# FlightControl.net
KiCad netlist of a schematic drawn in EAGLE
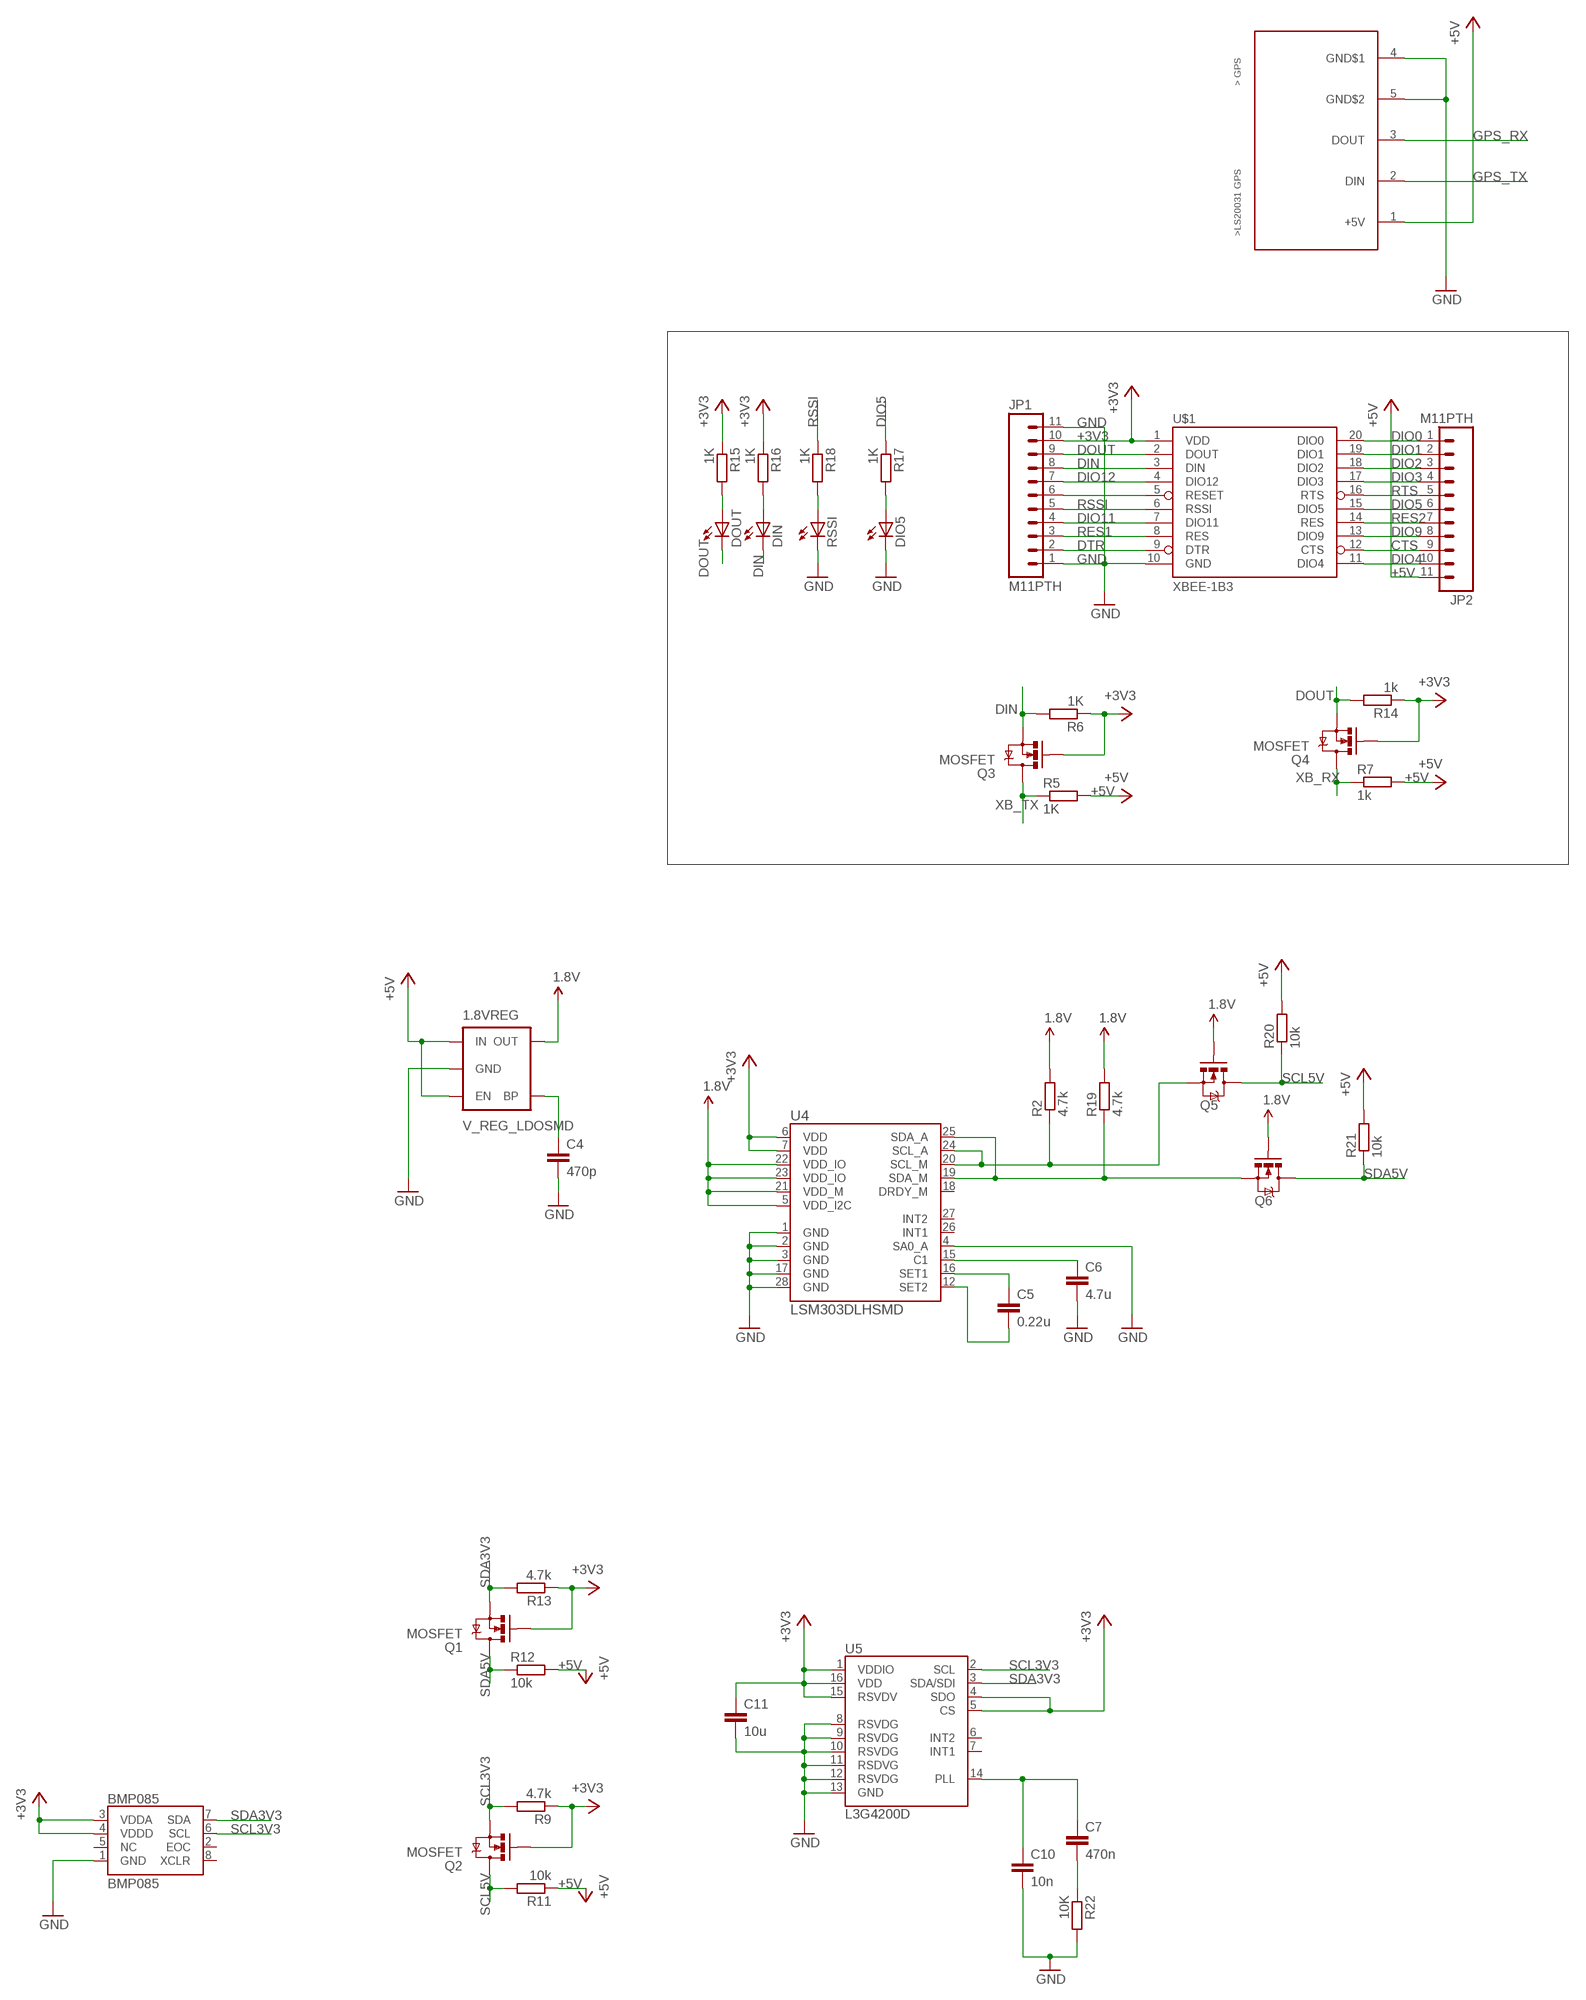
[diagram p0: schematic, sheet 1, part 1 of 2]
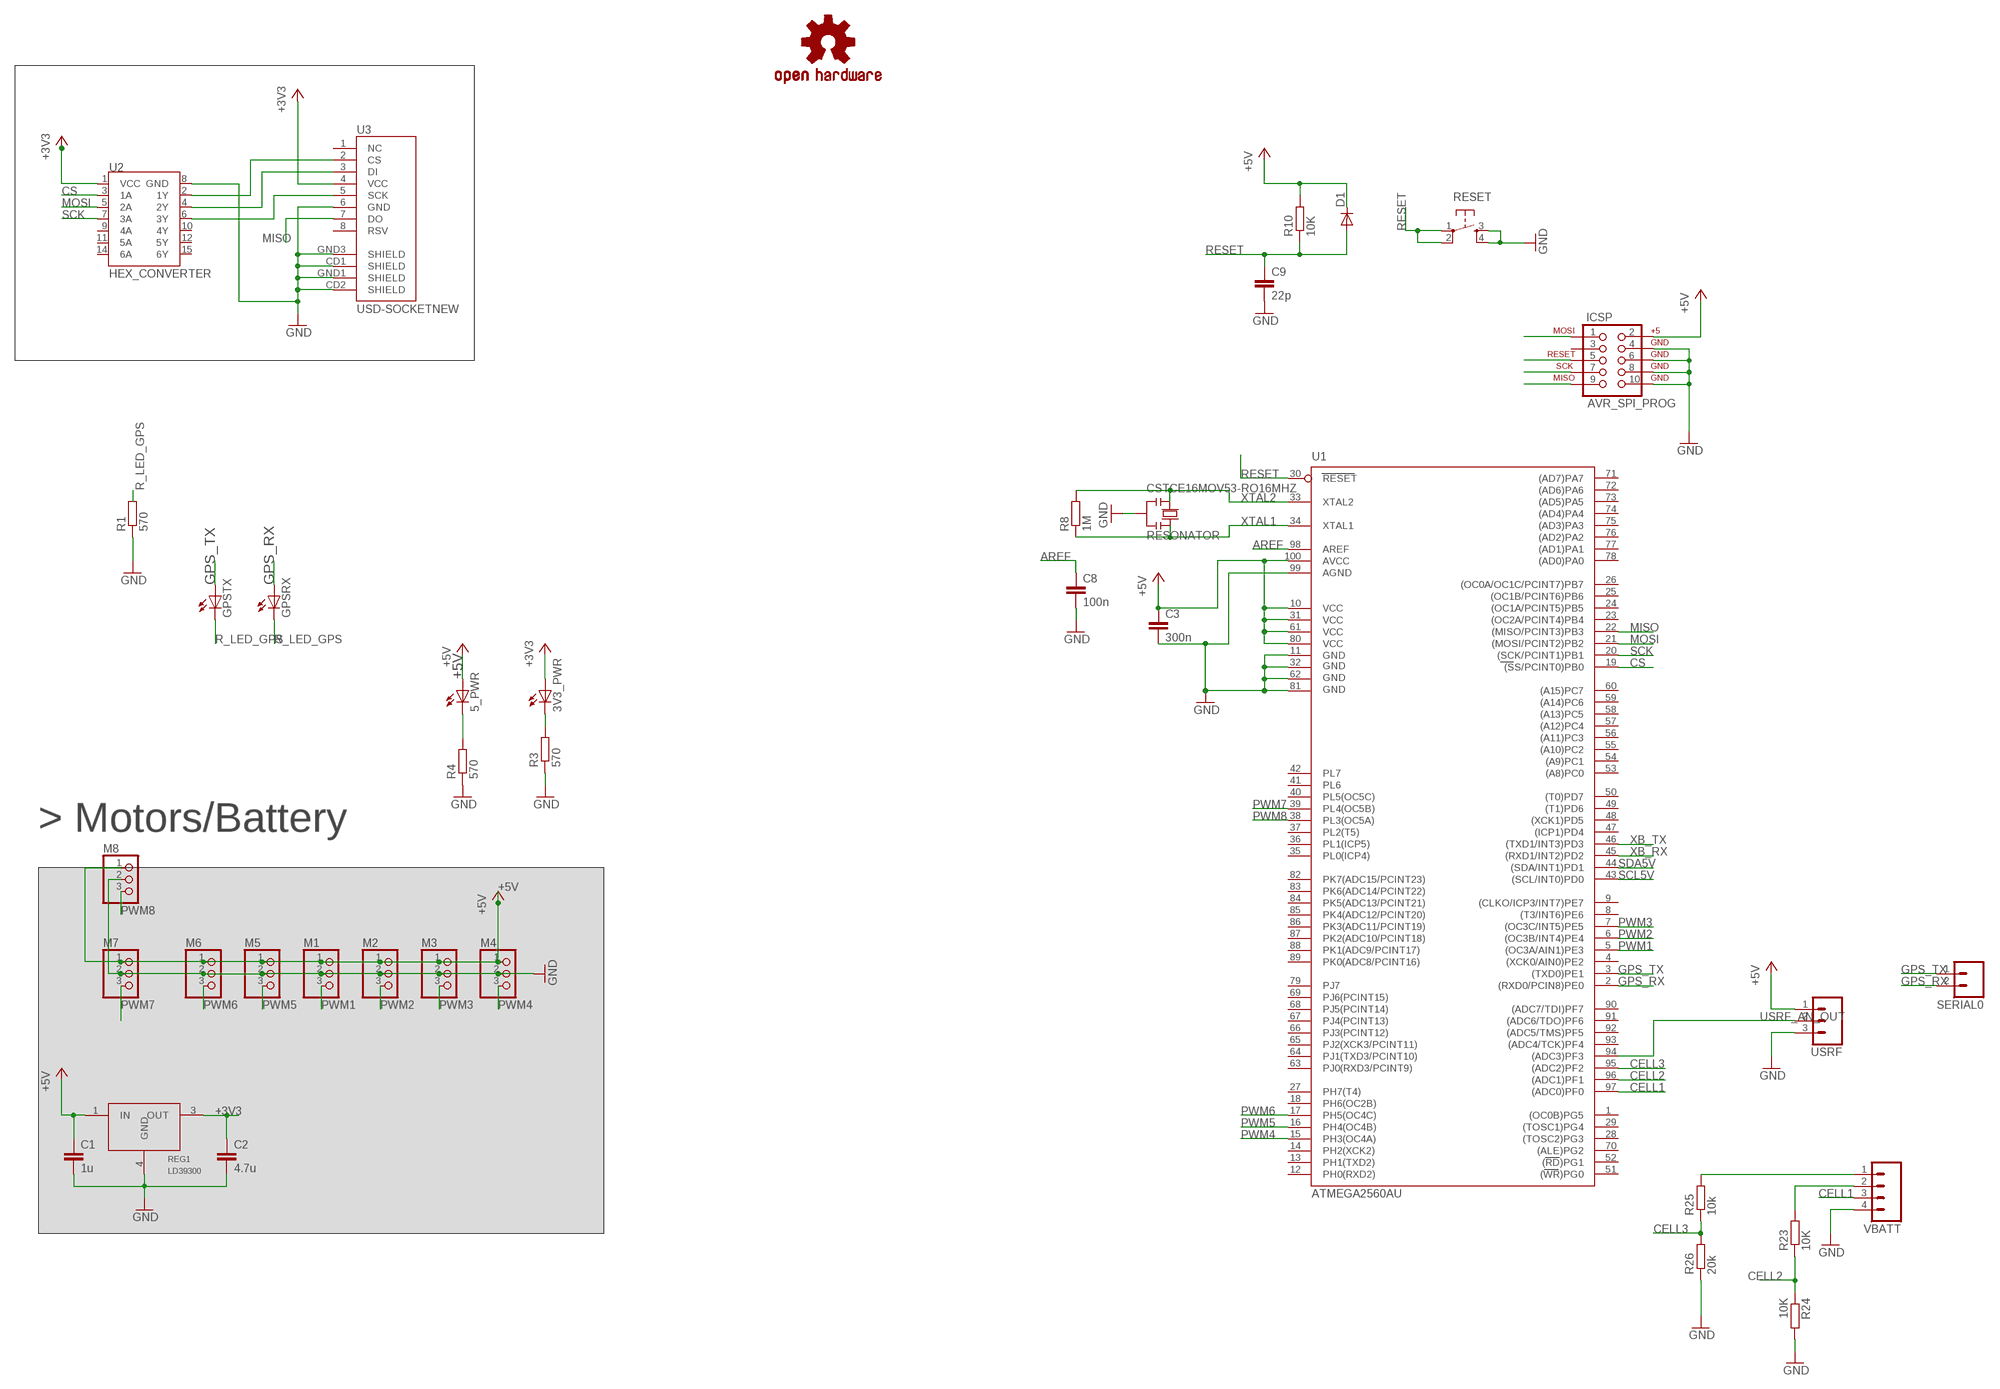
[diagram p1: schematic, sheet 1, part 2 of 2]

(export (version "E")
  (design (tool "Eeschema 10.0.6"))
  (components
    (comp (ref "1.8VREG")
      (value "V_REG_LDOSMD")
      (footprint "eagle-import:SOT23-5")
      (libsource (lib "eagle-import") (part "V_REG_LDOSMD"))
    )
    (comp (ref "3V3_PWR")
      (value "LEDCHIPLED_1206")
      (footprint "eagle-import:CHIPLED_1206")
      (libsource (lib "eagle-import") (part "LEDCHIPLED_1206"))
    )
    (comp (ref "5_PWR")
      (value "LEDCHIPLED_1206")
      (footprint "eagle-import:CHIPLED_1206")
      (libsource (lib "eagle-import") (part "LEDCHIPLED_1206"))
    )
    (comp (ref "BMP085")
      (value "BMP085")
      (footprint "eagle-import:BMP085")
      (libsource (lib "eagle-import") (part "BMP085"))
    )
    (comp (ref "C1")
      (value "1u")
      (footprint "eagle-import:C3216")
      (libsource (lib "eagle-import") (part "C-EUC3216"))
    )
    (comp (ref "C2")
      (value "4.7u")
      (footprint "eagle-import:C3216")
      (libsource (lib "eagle-import") (part "C-EUC3216"))
    )
    (comp (ref "C3")
      (value "300n")
      (footprint "eagle-import:C3216")
      (libsource (lib "eagle-import") (part "C-EUC3216"))
    )
    (comp (ref "C4")
      (value "470p")
      (footprint "eagle-import:C3216")
      (libsource (lib "eagle-import") (part "C-EUC3216"))
    )
    (comp (ref "C5")
      (value "0.22u")
      (footprint "eagle-import:C3216")
      (libsource (lib "eagle-import") (part "C-EUC3216"))
    )
    (comp (ref "C6")
      (value "4.7u")
      (footprint "eagle-import:C3216")
      (libsource (lib "eagle-import") (part "C-EUC3216"))
    )
    (comp (ref "C7")
      (value "470n")
      (footprint "eagle-import:C3216")
      (libsource (lib "eagle-import") (part "C-EUC3216"))
    )
    (comp (ref "C8")
      (value "100n")
      (footprint "eagle-import:C3216")
      (libsource (lib "eagle-import") (part "C-EUC3216"))
    )
    (comp (ref "C9")
      (value "22p")
      (footprint "eagle-import:C3216")
      (libsource (lib "eagle-import") (part "C-EUC3216"))
    )
    (comp (ref "C10")
      (value "10n")
      (footprint "eagle-import:C3216")
      (libsource (lib "eagle-import") (part "C-EUC3216"))
    )
    (comp (ref "C11")
      (value "10u")
      (footprint "eagle-import:C3216")
      (libsource (lib "eagle-import") (part "C-EUC3216"))
    )
    (comp (ref "CSTCE16MOV53-RO16MHZ")
      (value "RESONATOR")
      (footprint "eagle-import:RESONATOR")
      (libsource (lib "eagle-import") (part "RESONATORMU"))
    )
    (comp (ref "D1")
      (value "DIODE-MINIMELF")
      (footprint "eagle-import:MINIMELF")
      (libsource (lib "eagle-import") (part "DIODE-MINIMELF"))
    )
    (comp (ref "DIN")
      (value "LEDCHIPLED_1206")
      (footprint "eagle-import:CHIPLED_1206")
      (libsource (lib "eagle-import") (part "LEDCHIPLED_1206"))
    )
    (comp (ref "DIO5")
      (value "LEDCHIPLED_1206")
      (footprint "eagle-import:CHIPLED_1206")
      (libsource (lib "eagle-import") (part "LEDCHIPLED_1206"))
    )
    (comp (ref "DOUT")
      (value "LEDCHIPLED_1206")
      (footprint "eagle-import:CHIPLED_1206")
      (libsource (lib "eagle-import") (part "LEDCHIPLED_1206"))
    )
    (comp (ref "GPSRX")
      (value "LEDCHIPLED_1206")
      (footprint "eagle-import:CHIPLED_1206")
      (libsource (lib "eagle-import") (part "LEDCHIPLED_1206"))
    )
    (comp (ref "GPSTX")
      (value "LEDCHIPLED_1206")
      (footprint "eagle-import:CHIPLED_1206")
      (libsource (lib "eagle-import") (part "LEDCHIPLED_1206"))
    )
    (comp (ref "ICSP")
      (value "AVR_SPI_PROG")
      (footprint "eagle-import:AVR_ICSP")
      (libsource (lib "eagle-import") (part "AVR_SPI_PROG"))
    )
    (comp (ref "JP1")
      (value "M11PTH")
      (footprint "eagle-import:1X11")
      (libsource (lib "eagle-import") (part "M11PTH"))
    )
    (comp (ref "JP2")
      (value "M11PTH")
      (footprint "eagle-import:1X11")
      (libsource (lib "eagle-import") (part "M11PTH"))
    )
    (comp (ref "LOGO1")
      (value "OSHW-LOGOL")
      (footprint "eagle-import:OSHW-LOGO-L")
      (libsource (lib "eagle-import") (part "OSHW-LOGOL"))
    )
    (comp (ref "M1")
      (value "PINHD-1X3")
      (footprint "eagle-import:1X03")
      (libsource (lib "eagle-import") (part "PINHD-1X3"))
    )
    (comp (ref "M2")
      (value "PINHD-1X3")
      (footprint "eagle-import:1X03")
      (libsource (lib "eagle-import") (part "PINHD-1X3"))
    )
    (comp (ref "M3")
      (value "PINHD-1X3")
      (footprint "eagle-import:1X03")
      (libsource (lib "eagle-import") (part "PINHD-1X3"))
    )
    (comp (ref "M4")
      (value "PINHD-1X3")
      (footprint "eagle-import:1X03")
      (libsource (lib "eagle-import") (part "PINHD-1X3"))
    )
    (comp (ref "M5")
      (value "PINHD-1X3")
      (footprint "eagle-import:1X03")
      (libsource (lib "eagle-import") (part "PINHD-1X3"))
    )
    (comp (ref "M6")
      (value "PINHD-1X3")
      (footprint "eagle-import:1X03")
      (libsource (lib "eagle-import") (part "PINHD-1X3"))
    )
    (comp (ref "M7")
      (value "PINHD-1X3")
      (footprint "eagle-import:1X03")
      (libsource (lib "eagle-import") (part "PINHD-1X3"))
    )
    (comp (ref "M8")
      (value "PINHD-1X3")
      (footprint "eagle-import:1X03")
      (libsource (lib "eagle-import") (part "PINHD-1X3"))
    )
    (comp (ref "Q1")
      (value "MOSFET")
      (footprint "eagle-import:SOT23")
      (libsource (lib "eagle-import") (part "MOSFET-NCHANNELBSS138"))
    )
    (comp (ref "Q2")
      (value "MOSFET")
      (footprint "eagle-import:SOT23")
      (libsource (lib "eagle-import") (part "MOSFET-NCHANNELBSS138"))
    )
    (comp (ref "Q3")
      (value "MOSFET")
      (footprint "eagle-import:SOT23")
      (libsource (lib "eagle-import") (part "MOSFET-NCHANNELBSS138"))
    )
    (comp (ref "Q4")
      (value "MOSFET")
      (footprint "eagle-import:SOT23")
      (libsource (lib "eagle-import") (part "MOSFET-NCHANNELBSS138"))
    )
    (comp (ref "Q5")
      (value "MOSFET")
      (footprint "eagle-import:SOT23")
      (libsource (lib "eagle-import") (part "MOSFET-NCHANNELBSS138"))
    )
    (comp (ref "Q6")
      (value "MOSFET")
      (footprint "eagle-import:SOT23")
      (libsource (lib "eagle-import") (part "MOSFET-NCHANNELBSS138"))
    )
    (comp (ref "R1")
      (value "570")
      (footprint "eagle-import:R1206")
      (libsource (lib "eagle-import") (part "R-EU_R1206"))
    )
    (comp (ref "R2")
      (value "4.7k")
      (footprint "eagle-import:R1206")
      (libsource (lib "eagle-import") (part "R-EU_R1206"))
    )
    (comp (ref "R3")
      (value "570")
      (footprint "eagle-import:R1206")
      (libsource (lib "eagle-import") (part "R-EU_R1206"))
    )
    (comp (ref "R4")
      (value "570")
      (footprint "eagle-import:R1206")
      (libsource (lib "eagle-import") (part "R-EU_R1206"))
    )
    (comp (ref "R5")
      (value "1K")
      (footprint "eagle-import:R1206")
      (libsource (lib "eagle-import") (part "R-EU_R1206"))
    )
    (comp (ref "R6")
      (value "1K")
      (footprint "eagle-import:R1206")
      (libsource (lib "eagle-import") (part "R-EU_R1206"))
    )
    (comp (ref "R7")
      (value "1k")
      (footprint "eagle-import:R1206")
      (libsource (lib "eagle-import") (part "R-EU_R1206"))
    )
    (comp (ref "R8")
      (value "1M")
      (footprint "eagle-import:R1206")
      (libsource (lib "eagle-import") (part "R-EU_R1206"))
    )
    (comp (ref "R9")
      (value "4.7k")
      (footprint "eagle-import:R1206")
      (libsource (lib "eagle-import") (part "R-EU_R1206"))
    )
    (comp (ref "R10")
      (value "10K")
      (footprint "eagle-import:R1206")
      (libsource (lib "eagle-import") (part "R-EU_R1206"))
    )
    (comp (ref "R11")
      (value "10k")
      (footprint "eagle-import:R1206")
      (libsource (lib "eagle-import") (part "R-EU_R1206"))
    )
    (comp (ref "R12")
      (value "10k")
      (footprint "eagle-import:R1206")
      (libsource (lib "eagle-import") (part "R-EU_R1206"))
    )
    (comp (ref "R13")
      (value "4.7k")
      (footprint "eagle-import:R1206")
      (libsource (lib "eagle-import") (part "R-EU_R1206"))
    )
    (comp (ref "R14")
      (value "1k")
      (footprint "eagle-import:R1206")
      (libsource (lib "eagle-import") (part "R-EU_R1206"))
    )
    (comp (ref "R15")
      (value "1K")
      (footprint "eagle-import:R1206")
      (libsource (lib "eagle-import") (part "R-EU_R1206"))
    )
    (comp (ref "R16")
      (value "1K")
      (footprint "eagle-import:R1206")
      (libsource (lib "eagle-import") (part "R-EU_R1206"))
    )
    (comp (ref "R17")
      (value "1K")
      (footprint "eagle-import:R1206")
      (libsource (lib "eagle-import") (part "R-EU_R1206"))
    )
    (comp (ref "R18")
      (value "1K")
      (footprint "eagle-import:R1206")
      (libsource (lib "eagle-import") (part "R-EU_R1206"))
    )
    (comp (ref "R19")
      (value "4.7k")
      (footprint "eagle-import:R1206")
      (libsource (lib "eagle-import") (part "R-EU_R1206"))
    )
    (comp (ref "R20")
      (value "10k")
      (footprint "eagle-import:R1206")
      (libsource (lib "eagle-import") (part "R-EU_R1206"))
    )
    (comp (ref "R21")
      (value "10k")
      (footprint "eagle-import:R1206")
      (libsource (lib "eagle-import") (part "R-EU_R1206"))
    )
    (comp (ref "R22")
      (value "10K")
      (footprint "eagle-import:R1206")
      (libsource (lib "eagle-import") (part "R-EU_R1206"))
    )
    (comp (ref "R23")
      (value "10K")
      (footprint "eagle-import:R1206")
      (libsource (lib "eagle-import") (part "R-EU_R1206"))
    )
    (comp (ref "R24")
      (value "10K")
      (footprint "eagle-import:R1206")
      (libsource (lib "eagle-import") (part "R-EU_R1206"))
    )
    (comp (ref "R25")
      (value "10k")
      (footprint "eagle-import:R1206")
      (libsource (lib "eagle-import") (part "R-EU_R1206"))
    )
    (comp (ref "R26")
      (value "20k")
      (footprint "eagle-import:R1206")
      (libsource (lib "eagle-import") (part "R-EU_R1206"))
    )
    (comp (ref "REG1")
      (value "LD39300")
      (footprint "eagle-import:DPAK")
      (libsource (lib "eagle-import") (part "LD39300"))
    )
    (comp (ref "RESET")
      (value "TAC_SWITCHPTH")
      (footprint "eagle-import:TACTILE-PTH")
      (libsource (lib "eagle-import") (part "TAC_SWITCHPTH"))
    )
    (comp (ref "RSSI")
      (value "LEDCHIPLED_1206")
      (footprint "eagle-import:CHIPLED_1206")
      (libsource (lib "eagle-import") (part "LEDCHIPLED_1206"))
    )
    (comp (ref "SERIAL0")
      (value "M02LOCK_LONGPADS")
      (footprint "eagle-import:1X02_LOCK_LONGPADS")
      (libsource (lib "eagle-import") (part "M02LOCK_LONGPADS"))
    )
    (comp (ref "U$1")
      (value "XBEE-1B3")
      (footprint "eagle-import:XBEE-SMD")
      (libsource (lib "eagle-import") (part "XBEE-1B3"))
    )
    (comp (ref "U$2")
      (value "LS20031")
      (footprint "eagle-import:LS20031")
      (libsource (lib "eagle-import") (part "LS20031"))
    )
    (comp (ref "U1")
      (value "ATMEGA2560AU")
      (footprint "eagle-import:TQFP100")
      (libsource (lib "eagle-import") (part "ATMEGA2560AU"))
    )
    (comp (ref "U2")
      (value "HEX_CONVERTER")
      (footprint "eagle-import:SO016")
      (libsource (lib "eagle-import") (part "HEX_CONVERTER"))
    )
    (comp (ref "U3")
      (value "USD-SOCKETNEW")
      (footprint "eagle-import:MICRO-SD-SOCKET-PP")
      (libsource (lib "eagle-import") (part "USD-SOCKETNEW"))
    )
    (comp (ref "U4")
      (value "LSM303DLHSMD")
      (footprint "eagle-import:LGA28-5X5")
      (libsource (lib "eagle-import") (part "LSM303DLHSMD"))
    )
    (comp (ref "U5")
      (value "L3G4200D")
      (footprint "eagle-import:LGA16-4X4")
      (libsource (lib "eagle-import") (part "L3G4200D"))
    )
    (comp (ref "USRF")
      (value "M03LONGPADS")
      (footprint "eagle-import:1X03_LONGPADS")
      (libsource (lib "eagle-import") (part "M03LONGPADS"))
    )
    (comp (ref "VBATT")
      (value "M04LONGPADS")
      (footprint "eagle-import:1X04_LONGPADS")
      (libsource (lib "eagle-import") (part "M04LONGPADS"))
    )
  )
  (nets
    (net (code "1") (name "+3V3") (class "Default")
      (node (ref "3V3_PWR") (pin "A") (pinfunction "A_A") (pintype "passive"))
      (node (ref "BMP085") (pin "3") (pinfunction "VDDA_3") (pintype "power_in"))
      (node (ref "BMP085") (pin "4") (pinfunction "VDDD_4") (pintype "power_in"))
      (node (ref "C11") (pin "1") (pinfunction "1_1") (pintype "passive"))
      (node (ref "C2") (pin "1") (pinfunction "1_1") (pintype "passive"))
      (node (ref "JP1") (pin "10") (pinfunction "10_10") (pintype "passive"))
      (node (ref "Q1") (pin "1") (pinfunction "G_1") (pintype "passive"))
      (node (ref "Q2") (pin "1") (pinfunction "G_1") (pintype "passive"))
      (node (ref "Q3") (pin "1") (pinfunction "G_1") (pintype "passive"))
      (node (ref "Q4") (pin "1") (pinfunction "G_1") (pintype "passive"))
      (node (ref "R13") (pin "1") (pinfunction "1_1") (pintype "passive"))
      (node (ref "R14") (pin "1") (pinfunction "1_1") (pintype "passive"))
      (node (ref "R15") (pin "1") (pinfunction "1_1") (pintype "passive"))
      (node (ref "R16") (pin "1") (pinfunction "1_1") (pintype "passive"))
      (node (ref "R6") (pin "1") (pinfunction "1_1") (pintype "passive"))
      (node (ref "R9") (pin "1") (pinfunction "1_1") (pintype "passive"))
      (node (ref "REG1") (pin "3") (pinfunction "OUT_3") (pintype "bidirectional"))
      (node (ref "U$1") (pin "1") (pinfunction "VDD_1") (pintype "power_in"))
      (node (ref "U2") (pin "1") (pinfunction "VCC_1") (pintype "bidirectional"))
      (node (ref "U3") (pin "4") (pinfunction "VCC_4") (pintype "bidirectional"))
      (node (ref "U4") (pin "6") (pinfunction "VDD_6") (pintype "bidirectional"))
      (node (ref "U4") (pin "7") (pinfunction "VDD_7") (pintype "bidirectional"))
      (node (ref "U5") (pin "1") (pinfunction "VDDIO_1") (pintype "bidirectional"))
      (node (ref "U5") (pin "15") (pinfunction "RSVDV_15") (pintype "bidirectional"))
      (node (ref "U5") (pin "16") (pinfunction "VDD_16") (pintype "bidirectional"))
      (node (ref "U5") (pin "4") (pinfunction "SDO_4") (pintype "bidirectional"))
      (node (ref "U5") (pin "5") (pinfunction "CS_5") (pintype "bidirectional"))
    )
    (net (code "2") (name "+5V") (class "Default")
      (node (ref "1.8VREG") (pin "1") (pinfunction "IN_1") (pintype "input"))
      (node (ref "1.8VREG") (pin "3") (pinfunction "EN_3") (pintype "input"))
      (node (ref "5_PWR") (pin "A") (pinfunction "A_A") (pintype "passive"))
      (node (ref "C1") (pin "1") (pinfunction "1_1") (pintype "passive"))
      (node (ref "C3") (pin "1") (pinfunction "1_1") (pintype "passive"))
      (node (ref "D1") (pin "C") (pinfunction "C_C") (pintype "passive"))
      (node (ref "ICSP") (pin "2") (pinfunction "2_2") (pintype "passive"))
      (node (ref "JP2") (pin "11") (pinfunction "11_11") (pintype "passive"))
      (node (ref "M1") (pin "1") (pinfunction "1_1") (pintype "passive"))
      (node (ref "M2") (pin "1") (pinfunction "1_1") (pintype "passive"))
      (node (ref "M3") (pin "1") (pinfunction "1_1") (pintype "passive"))
      (node (ref "M4") (pin "1") (pinfunction "1_1") (pintype "passive"))
      (node (ref "M5") (pin "1") (pinfunction "1_1") (pintype "passive"))
      (node (ref "M6") (pin "1") (pinfunction "1_1") (pintype "passive"))
      (node (ref "M7") (pin "1") (pinfunction "1_1") (pintype "passive"))
      (node (ref "M8") (pin "1") (pinfunction "1_1") (pintype "passive"))
      (node (ref "R10") (pin "2") (pinfunction "2_2") (pintype "passive"))
      (node (ref "R11") (pin "1") (pinfunction "1_1") (pintype "passive"))
      (node (ref "R12") (pin "2") (pinfunction "2_2") (pintype "passive"))
      (node (ref "R20") (pin "2") (pinfunction "2_2") (pintype "passive"))
      (node (ref "R21") (pin "2") (pinfunction "2_2") (pintype "passive"))
      (node (ref "R5") (pin "2") (pinfunction "2_2") (pintype "passive"))
      (node (ref "R7") (pin "2") (pinfunction "2_2") (pintype "passive"))
      (node (ref "REG1") (pin "1") (pinfunction "IN_1") (pintype "bidirectional"))
      (node (ref "U$2") (pin "1") (pinfunction "+5V_1") (pintype "bidirectional"))
      (node (ref "U1") (pin "10") (pinfunction "VCC_10") (pintype "power_in"))
      (node (ref "U1") (pin "100") (pinfunction "AVCC_100") (pintype "power_in"))
      (node (ref "U1") (pin "31") (pinfunction "VCC1_31") (pintype "power_in"))
      (node (ref "U1") (pin "61") (pinfunction "VCC2_61") (pintype "power_in"))
      (node (ref "U1") (pin "80") (pinfunction "VCC3_80") (pintype "power_in"))
      (node (ref "USRF") (pin "1") (pinfunction "1_1") (pintype "passive"))
    )
    (net (code "3") (name "/AREF") (class "Default")
      (node (ref "C8") (pin "1") (pinfunction "1_1") (pintype "passive"))
      (node (ref "U1") (pin "98") (pinfunction "AREF_98") (pintype "bidirectional"))
    )
    (net (code "4") (name "/CELL1") (class "Default")
      (node (ref "U1") (pin "97") (pinfunction "(ADC0)PF0_97") (pintype "bidirectional"))
      (node (ref "VBATT") (pin "3") (pinfunction "3_3") (pintype "passive"))
    )
    (net (code "5") (name "/CELL2") (class "Default")
      (node (ref "R23") (pin "1") (pinfunction "1_1") (pintype "passive"))
      (node (ref "R24") (pin "1") (pinfunction "1_1") (pintype "passive"))
      (node (ref "U1") (pin "96") (pinfunction "(ADC1)PF1_96") (pintype "bidirectional"))
    )
    (net (code "6") (name "/CELL3") (class "Default")
      (node (ref "R25") (pin "1") (pinfunction "1_1") (pintype "passive"))
      (node (ref "R26") (pin "2") (pinfunction "2_2") (pintype "passive"))
      (node (ref "U1") (pin "95") (pinfunction "(ADC2)PF2_95") (pintype "bidirectional"))
    )
    (net (code "7") (name "/CS") (class "Default")
      (node (ref "U1") (pin "19") (pinfunction "(SS/PCINT0)PB0_19") (pintype "bidirectional"))
      (node (ref "U2") (pin "3") (pinfunction "1A_3") (pintype "bidirectional"))
    )
    (net (code "8") (name "/CTS") (class "Default")
      (node (ref "JP2") (pin "9") (pinfunction "9_9") (pintype "passive"))
      (node (ref "U$1") (pin "12") (pinfunction "CTS_12") (pintype "output"))
    )
    (net (code "9") (name "/DIN") (class "Default")
      (node (ref "DIN") (pin "C") (pinfunction "C_C") (pintype "passive"))
      (node (ref "JP1") (pin "8") (pinfunction "8_8") (pintype "passive"))
      (node (ref "Q3") (pin "2") (pinfunction "S_2") (pintype "passive"))
      (node (ref "R6") (pin "2") (pinfunction "2_2") (pintype "passive"))
      (node (ref "U$1") (pin "3") (pinfunction "DIN_3") (pintype "input"))
    )
    (net (code "10") (name "/DIO0") (class "Default")
      (node (ref "JP2") (pin "1") (pinfunction "1_1") (pintype "passive"))
      (node (ref "U$1") (pin "20") (pinfunction "DIO0_20") (pintype "bidirectional"))
    )
    (net (code "11") (name "/DIO1") (class "Default")
      (node (ref "JP2") (pin "2") (pinfunction "2_2") (pintype "passive"))
      (node (ref "U$1") (pin "19") (pinfunction "DIO1_19") (pintype "bidirectional"))
    )
    (net (code "12") (name "/DIO2") (class "Default")
      (node (ref "JP2") (pin "3") (pinfunction "3_3") (pintype "passive"))
      (node (ref "U$1") (pin "18") (pinfunction "DIO2_18") (pintype "bidirectional"))
    )
    (net (code "13") (name "/DIO3") (class "Default")
      (node (ref "JP2") (pin "4") (pinfunction "4_4") (pintype "passive"))
      (node (ref "U$1") (pin "17") (pinfunction "DIO3_17") (pintype "bidirectional"))
    )
    (net (code "14") (name "/DIO4") (class "Default")
      (node (ref "JP2") (pin "10") (pinfunction "10_10") (pintype "passive"))
      (node (ref "U$1") (pin "11") (pinfunction "DIO4_11") (pintype "bidirectional"))
    )
    (net (code "15") (name "/DIO5") (class "Default")
      (node (ref "JP2") (pin "6") (pinfunction "6_6") (pintype "passive"))
      (node (ref "R17") (pin "1") (pinfunction "1_1") (pintype "passive"))
      (node (ref "U$1") (pin "15") (pinfunction "DIO5_15") (pintype "bidirectional"))
    )
    (net (code "16") (name "/DIO9") (class "Default")
      (node (ref "JP2") (pin "8") (pinfunction "8_8") (pintype "passive"))
      (node (ref "U$1") (pin "13") (pinfunction "DIO9_13") (pintype "bidirectional"))
    )
    (net (code "17") (name "/DIO11") (class "Default")
      (node (ref "JP1") (pin "4") (pinfunction "4_4") (pintype "passive"))
      (node (ref "U$1") (pin "7") (pinfunction "DIO11_7") (pintype "bidirectional"))
    )
    (net (code "18") (name "/DIO12") (class "Default")
      (node (ref "JP1") (pin "7") (pinfunction "7_7") (pintype "passive"))
      (node (ref "U$1") (pin "4") (pinfunction "DIO12_4") (pintype "bidirectional"))
    )
    (net (code "19") (name "/DOUT") (class "Default")
      (node (ref "DOUT") (pin "C") (pinfunction "C_C") (pintype "passive"))
      (node (ref "JP1") (pin "9") (pinfunction "9_9") (pintype "passive"))
      (node (ref "Q4") (pin "2") (pinfunction "S_2") (pintype "passive"))
      (node (ref "R14") (pin "2") (pinfunction "2_2") (pintype "passive"))
      (node (ref "U$1") (pin "2") (pinfunction "DOUT_2") (pintype "output"))
    )
    (net (code "20") (name "/DTR") (class "Default")
      (node (ref "JP1") (pin "2") (pinfunction "2_2") (pintype "passive"))
      (node (ref "U$1") (pin "9") (pinfunction "DTR_9") (pintype "bidirectional"))
    )
    (net (code "21") (name "/GPS_RX") (class "Default")
      (node (ref "GPSRX") (pin "A") (pinfunction "A_A") (pintype "passive"))
      (node (ref "SERIAL0") (pin "2") (pinfunction "2_2") (pintype "passive"))
      (node (ref "U$2") (pin "3") (pinfunction "DOUT_3") (pintype "output"))
      (node (ref "U1") (pin "2") (pinfunction "(RXD0/PCIN8)PE0_2") (pintype "bidirectional"))
    )
    (net (code "22") (name "/GPS_TX") (class "Default")
      (node (ref "GPSTX") (pin "A") (pinfunction "A_A") (pintype "passive"))
      (node (ref "SERIAL0") (pin "1") (pinfunction "1_1") (pintype "passive"))
      (node (ref "U$2") (pin "2") (pinfunction "DIN_2") (pintype "bidirectional"))
      (node (ref "U1") (pin "3") (pinfunction "(TXD0)PE1_3") (pintype "bidirectional"))
    )
    (net (code "23") (name "/MISO") (class "Default")
      (node (ref "ICSP") (pin "9") (pinfunction "9_9") (pintype "passive"))
      (node (ref "U1") (pin "22") (pinfunction "(MISO/PCINT3)PB3_22") (pintype "bidirectional"))
      (node (ref "U3") (pin "7") (pinfunction "DO_7") (pintype "bidirectional"))
    )
    (net (code "24") (name "/MOSI") (class "Default")
      (node (ref "ICSP") (pin "1") (pinfunction "1_1") (pintype "passive"))
      (node (ref "U1") (pin "21") (pinfunction "(MOSI/PCINT2)PB2_21") (pintype "bidirectional"))
      (node (ref "U2") (pin "5") (pinfunction "2A_5") (pintype "bidirectional"))
    )
    (net (code "25") (name "/PWM1") (class "Default")
      (node (ref "M1") (pin "3") (pinfunction "3_3") (pintype "passive"))
      (node (ref "U1") (pin "5") (pinfunction "(OC3A/AIN1)PE3_5") (pintype "bidirectional"))
    )
    (net (code "26") (name "/PWM2") (class "Default")
      (node (ref "M2") (pin "3") (pinfunction "3_3") (pintype "passive"))
      (node (ref "U1") (pin "6") (pinfunction "(OC3B/INT4)PE4_6") (pintype "bidirectional"))
    )
    (net (code "27") (name "/PWM3") (class "Default")
      (node (ref "M3") (pin "3") (pinfunction "3_3") (pintype "passive"))
      (node (ref "U1") (pin "7") (pinfunction "(OC3C/INT5)PE5_7") (pintype "bidirectional"))
    )
    (net (code "28") (name "/PWM4") (class "Default")
      (node (ref "M4") (pin "3") (pinfunction "3_3") (pintype "passive"))
      (node (ref "U1") (pin "15") (pinfunction "PH3(OC4A)_15") (pintype "bidirectional"))
    )
    (net (code "29") (name "/PWM5") (class "Default")
      (node (ref "M5") (pin "3") (pinfunction "3_3") (pintype "passive"))
      (node (ref "U1") (pin "16") (pinfunction "PH4(OC4B)_16") (pintype "bidirectional"))
    )
    (net (code "30") (name "/PWM6") (class "Default")
      (node (ref "M6") (pin "3") (pinfunction "3_3") (pintype "passive"))
      (node (ref "U1") (pin "17") (pinfunction "PH5(OC4C)_17") (pintype "bidirectional"))
    )
    (net (code "31") (name "/PWM7") (class "Default")
      (node (ref "M7") (pin "3") (pinfunction "3_3") (pintype "passive"))
      (node (ref "U1") (pin "39") (pinfunction "PL4(OC5B)_39") (pintype "bidirectional"))
    )
    (net (code "32") (name "/PWM8") (class "Default")
      (node (ref "M8") (pin "3") (pinfunction "3_3") (pintype "passive"))
      (node (ref "U1") (pin "38") (pinfunction "PL3(OC5A)_38") (pintype "bidirectional"))
    )
    (net (code "33") (name "/RES1") (class "Default")
      (node (ref "JP1") (pin "3") (pinfunction "3_3") (pintype "passive"))
      (node (ref "U$1") (pin "8") (pinfunction "RES_8") (pintype "bidirectional"))
    )
    (net (code "34") (name "/RES2") (class "Default")
      (node (ref "JP2") (pin "7") (pinfunction "7_7") (pintype "passive"))
      (node (ref "U$1") (pin "14") (pinfunction "RES_14") (pintype "bidirectional"))
    )
    (net (code "35") (name "/RESET") (class "Default")
      (node (ref "C9") (pin "1") (pinfunction "1_1") (pintype "passive"))
      (node (ref "D1") (pin "A") (pinfunction "A_A") (pintype "passive"))
      (node (ref "ICSP") (pin "5") (pinfunction "5_5") (pintype "passive"))
      (node (ref "R10") (pin "1") (pinfunction "1_1") (pintype "passive"))
      (node (ref "RESET") (pin "1") (pinfunction "1_1") (pintype "passive"))
      (node (ref "RESET") (pin "2") (pinfunction "2_2") (pintype "passive"))
      (node (ref "U1") (pin "30") (pinfunction "RESET_30") (pintype "input"))
    )
    (net (code "36") (name "/RSSI") (class "Default")
      (node (ref "JP1") (pin "5") (pinfunction "5_5") (pintype "passive"))
      (node (ref "R18") (pin "1") (pinfunction "1_1") (pintype "passive"))
      (node (ref "U$1") (pin "6") (pinfunction "RSSI_6") (pintype "bidirectional"))
    )
    (net (code "37") (name "/RTS") (class "Default")
      (node (ref "JP2") (pin "5") (pinfunction "5_5") (pintype "passive"))
      (node (ref "U$1") (pin "16") (pinfunction "RTS_16") (pintype "input"))
    )
    (net (code "38") (name "/R_LED_GPS") (class "Default")
      (node (ref "GPSRX") (pin "C") (pinfunction "C_C") (pintype "passive"))
      (node (ref "GPSTX") (pin "C") (pinfunction "C_C") (pintype "passive"))
      (node (ref "R1") (pin "2") (pinfunction "2_2") (pintype "passive"))
    )
    (net (code "39") (name "/SCK") (class "Default")
      (node (ref "ICSP") (pin "7") (pinfunction "7_7") (pintype "passive"))
      (node (ref "U1") (pin "20") (pinfunction "(SCK/PCINT1)PB1_20") (pintype "bidirectional"))
      (node (ref "U2") (pin "7") (pinfunction "3A_7") (pintype "bidirectional"))
    )
    (net (code "40") (name "/SCL3V3") (class "Default")
      (node (ref "BMP085") (pin "6") (pinfunction "SCL_6") (pintype "input"))
      (node (ref "Q2") (pin "2") (pinfunction "S_2") (pintype "passive"))
      (node (ref "R9") (pin "2") (pinfunction "2_2") (pintype "passive"))
      (node (ref "U5") (pin "2") (pinfunction "SCL_2") (pintype "bidirectional"))
    )
    (net (code "41") (name "/SCL5V") (class "Default")
      (node (ref "Q2") (pin "3") (pinfunction "D_3") (pintype "passive"))
      (node (ref "Q5") (pin "3") (pinfunction "D_3") (pintype "passive"))
      (node (ref "R11") (pin "2") (pinfunction "2_2") (pintype "passive"))
      (node (ref "R20") (pin "1") (pinfunction "1_1") (pintype "passive"))
      (node (ref "U1") (pin "43") (pinfunction "(SCL/INT0)PD0_43") (pintype "bidirectional"))
    )
    (net (code "42") (name "/SDA3V3") (class "Default")
      (node (ref "BMP085") (pin "7") (pinfunction "SDA_7") (pintype "bidirectional"))
      (node (ref "Q1") (pin "2") (pinfunction "S_2") (pintype "passive"))
      (node (ref "R13") (pin "2") (pinfunction "2_2") (pintype "passive"))
      (node (ref "U5") (pin "3") (pinfunction "SDA/SDI_3") (pintype "bidirectional"))
    )
    (net (code "43") (name "/SDA5V") (class "Default")
      (node (ref "Q1") (pin "3") (pinfunction "D_3") (pintype "passive"))
      (node (ref "Q6") (pin "3") (pinfunction "D_3") (pintype "passive"))
      (node (ref "R12") (pin "1") (pinfunction "1_1") (pintype "passive"))
      (node (ref "R21") (pin "1") (pinfunction "1_1") (pintype "passive"))
      (node (ref "U1") (pin "44") (pinfunction "(SDA/INT1)PD1_44") (pintype "bidirectional"))
    )
    (net (code "44") (name "/USRF_AN_OUT") (class "Default")
      (node (ref "U1") (pin "94") (pinfunction "(ADC3)PF3_94") (pintype "bidirectional"))
      (node (ref "USRF") (pin "2") (pinfunction "2_2") (pintype "passive"))
    )
    (net (code "45") (name "/XB_RX") (class "Default")
      (node (ref "Q4") (pin "3") (pinfunction "D_3") (pintype "passive"))
      (node (ref "R7") (pin "1") (pinfunction "1_1") (pintype "passive"))
      (node (ref "U1") (pin "45") (pinfunction "(RXD1/INT2)PD2_45") (pintype "bidirectional"))
    )
    (net (code "46") (name "/XB_TX") (class "Default")
      (node (ref "Q3") (pin "3") (pinfunction "D_3") (pintype "passive"))
      (node (ref "R5") (pin "1") (pinfunction "1_1") (pintype "passive"))
      (node (ref "U1") (pin "46") (pinfunction "(TXD1/INT3)PD3_46") (pintype "bidirectional"))
    )
    (net (code "47") (name "/XTAL1") (class "Default")
      (node (ref "CSTCE16MOV53-RO16MHZ") (pin "3") (pinfunction "3_3") (pintype "passive"))
      (node (ref "R8") (pin "1") (pinfunction "1_1") (pintype "passive"))
      (node (ref "U1") (pin "34") (pinfunction "XTAL1_34") (pintype "input"))
    )
    (net (code "48") (name "/XTAL2") (class "Default")
      (node (ref "CSTCE16MOV53-RO16MHZ") (pin "1") (pinfunction "1_1") (pintype "passive"))
      (node (ref "R8") (pin "2") (pinfunction "2_2") (pintype "passive"))
      (node (ref "U1") (pin "33") (pinfunction "XTAL2_33") (pintype "output"))
    )
    (net (code "49") (name "1.8V") (class "Default")
      (node (ref "1.8VREG") (pin "5") (pinfunction "OUT_5") (pintype "passive"))
      (node (ref "Q5") (pin "1") (pinfunction "G_1") (pintype "passive"))
      (node (ref "Q6") (pin "1") (pinfunction "G_1") (pintype "passive"))
      (node (ref "R19") (pin "2") (pinfunction "2_2") (pintype "passive"))
      (node (ref "R2") (pin "2") (pinfunction "2_2") (pintype "passive"))
      (node (ref "U4") (pin "21") (pinfunction "VDD_M_21") (pintype "bidirectional"))
      (node (ref "U4") (pin "22") (pinfunction "VDD_IO_22") (pintype "bidirectional"))
      (node (ref "U4") (pin "23") (pinfunction "VDD_IO_23") (pintype "bidirectional"))
      (node (ref "U4") (pin "5") (pinfunction "VDD_I2C_5") (pintype "bidirectional"))
    )
    (net (code "50") (name "GND") (class "Default")
      (node (ref "1.8VREG") (pin "2") (pinfunction "GND_2") (pintype "input"))
      (node (ref "BMP085") (pin "1") (pinfunction "GND_1") (pintype "power_in"))
      (node (ref "C1") (pin "2") (pinfunction "2_2") (pintype "passive"))
      (node (ref "C10") (pin "2") (pinfunction "2_2") (pintype "passive"))
      (node (ref "C11") (pin "2") (pinfunction "2_2") (pintype "passive"))
      (node (ref "C2") (pin "2") (pinfunction "2_2") (pintype "passive"))
      (node (ref "C3") (pin "2") (pinfunction "2_2") (pintype "passive"))
      (node (ref "C4") (pin "2") (pinfunction "2_2") (pintype "passive"))
      (node (ref "C6") (pin "2") (pinfunction "2_2") (pintype "passive"))
      (node (ref "C8") (pin "2") (pinfunction "2_2") (pintype "passive"))
      (node (ref "C9") (pin "2") (pinfunction "2_2") (pintype "passive"))
      (node (ref "CSTCE16MOV53-RO16MHZ") (pin "2") (pinfunction "2_2") (pintype "passive"))
      (node (ref "DIO5") (pin "C") (pinfunction "C_C") (pintype "passive"))
      (node (ref "ICSP") (pin "10") (pinfunction "10_10") (pintype "passive"))
      (node (ref "ICSP") (pin "4") (pinfunction "4_4") (pintype "passive"))
      (node (ref "ICSP") (pin "6") (pinfunction "6_6") (pintype "passive"))
      (node (ref "ICSP") (pin "8") (pinfunction "8_8") (pintype "passive"))
      (node (ref "JP1") (pin "1") (pinfunction "1_1") (pintype "passive"))
      (node (ref "JP1") (pin "11") (pinfunction "11_11") (pintype "passive"))
      (node (ref "M1") (pin "2") (pinfunction "2_2") (pintype "passive"))
      (node (ref "M2") (pin "2") (pinfunction "2_2") (pintype "passive"))
      (node (ref "M3") (pin "2") (pinfunction "2_2") (pintype "passive"))
      (node (ref "M4") (pin "2") (pinfunction "2_2") (pintype "passive"))
      (node (ref "M5") (pin "2") (pinfunction "2_2") (pintype "passive"))
      (node (ref "M6") (pin "2") (pinfunction "2_2") (pintype "passive"))
      (node (ref "M7") (pin "2") (pinfunction "2_2") (pintype "passive"))
      (node (ref "M8") (pin "2") (pinfunction "2_2") (pintype "passive"))
      (node (ref "R1") (pin "1") (pinfunction "1_1") (pintype "passive"))
      (node (ref "R22") (pin "2") (pinfunction "2_2") (pintype "passive"))
      (node (ref "R24") (pin "2") (pinfunction "2_2") (pintype "passive"))
      (node (ref "R26") (pin "1") (pinfunction "1_1") (pintype "passive"))
      (node (ref "R3") (pin "1") (pinfunction "1_1") (pintype "passive"))
      (node (ref "R4") (pin "1") (pinfunction "1_1") (pintype "passive"))
      (node (ref "REG1") (pin "4") (pinfunction "GND_4") (pintype "bidirectional"))
      (node (ref "RESET") (pin "3") (pinfunction "3_3") (pintype "passive"))
      (node (ref "RESET") (pin "4") (pinfunction "4_4") (pintype "passive"))
      (node (ref "RSSI") (pin "C") (pinfunction "C_C") (pintype "passive"))
      (node (ref "U$1") (pin "10") (pinfunction "GND_10") (pintype "power_in"))
      (node (ref "U$2") (pin "4") (pinfunction "GND$1_4") (pintype "bidirectional"))
      (node (ref "U$2") (pin "5") (pinfunction "GND$2_5") (pintype "bidirectional"))
      (node (ref "U1") (pin "11") (pinfunction "GND_11") (pintype "power_in"))
      (node (ref "U1") (pin "32") (pinfunction "GND1_32") (pintype "power_in"))
      (node (ref "U1") (pin "62") (pinfunction "GND2_62") (pintype "power_in"))
      (node (ref "U1") (pin "81") (pinfunction "GND3_81") (pintype "power_in"))
      (node (ref "U1") (pin "99") (pinfunction "AGND_99") (pintype "power_in"))
      (node (ref "U2") (pin "8") (pinfunction "GND_8") (pintype "bidirectional"))
      (node (ref "U3") (pin "6") (pinfunction "GND_6") (pintype "bidirectional"))
      (node (ref "U3") (pin "CD1") (pinfunction "SHIELD_CD1") (pintype "bidirectional"))
      (node (ref "U3") (pin "CD2") (pinfunction "SHIELD_CD2") (pintype "bidirectional"))
      (node (ref "U3") (pin "GND1") (pinfunction "SHIELD_GND1") (pintype "bidirectional"))
      (node (ref "U3") (pin "GND3") (pinfunction "SHIELD_GND3") (pintype "bidirectional"))
      (node (ref "U4") (pin "1") (pinfunction "GND_1") (pintype "bidirectional"))
      (node (ref "U4") (pin "17") (pinfunction "GND_17") (pintype "bidirectional"))
      (node (ref "U4") (pin "2") (pinfunction "GND_2") (pintype "bidirectional"))
      (node (ref "U4") (pin "28") (pinfunction "GND_28") (pintype "bidirectional"))
      (node (ref "U4") (pin "3") (pinfunction "GND_3") (pintype "bidirectional"))
      (node (ref "U4") (pin "4") (pinfunction "SA0_A_4") (pintype "bidirectional"))
      (node (ref "U5") (pin "10") (pinfunction "RSVDG_10") (pintype "bidirectional"))
      (node (ref "U5") (pin "11") (pinfunction "RSDVG_11") (pintype "bidirectional"))
      (node (ref "U5") (pin "12") (pinfunction "RSVDG_12") (pintype "bidirectional"))
      (node (ref "U5") (pin "13") (pinfunction "GND_13") (pintype "bidirectional"))
      (node (ref "U5") (pin "8") (pinfunction "RSVDG_8") (pintype "bidirectional"))
      (node (ref "U5") (pin "9") (pinfunction "RSVDG_9") (pintype "bidirectional"))
      (node (ref "USRF") (pin "3") (pinfunction "3_3") (pintype "passive"))
      (node (ref "VBATT") (pin "4") (pinfunction "4_4") (pintype "passive"))
    )
    (net (code "51") (name "Net-(1.8VREG-BP)") (class "Default")
      (node (ref "1.8VREG") (pin "4") (pinfunction "BP_4") (pintype "input"))
      (node (ref "C4") (pin "1") (pinfunction "1_1") (pintype "passive"))
    )
    (net (code "52") (name "Net-(3V3_PWR-PadC)") (class "Default")
      (node (ref "3V3_PWR") (pin "C") (pinfunction "C_C") (pintype "passive"))
      (node (ref "R3") (pin "2") (pinfunction "2_2") (pintype "passive"))
    )
    (net (code "53") (name "Net-(5_PWR-PadC)") (class "Default")
      (node (ref "5_PWR") (pin "C") (pinfunction "C_C") (pintype "passive"))
      (node (ref "R4") (pin "2") (pinfunction "2_2") (pintype "passive"))
    )
    (net (code "54") (name "Net-(C7-Pad2)") (class "Default")
      (node (ref "C7") (pin "2") (pinfunction "2_2") (pintype "passive"))
      (node (ref "R22") (pin "1") (pinfunction "1_1") (pintype "passive"))
    )
    (net (code "55") (name "Net-(DIN-PadA)") (class "Default")
      (node (ref "DIN") (pin "A") (pinfunction "A_A") (pintype "passive"))
      (node (ref "R16") (pin "2") (pinfunction "2_2") (pintype "passive"))
    )
    (net (code "56") (name "Net-(DIO5-PadA)") (class "Default")
      (node (ref "DIO5") (pin "A") (pinfunction "A_A") (pintype "passive"))
      (node (ref "R17") (pin "2") (pinfunction "2_2") (pintype "passive"))
    )
    (net (code "57") (name "Net-(DOUT-PadA)") (class "Default")
      (node (ref "DOUT") (pin "A") (pinfunction "A_A") (pintype "passive"))
      (node (ref "R15") (pin "2") (pinfunction "2_2") (pintype "passive"))
    )
    (net (code "58") (name "Net-(Q5-S)") (class "Default")
      (node (ref "Q5") (pin "2") (pinfunction "S_2") (pintype "passive"))
      (node (ref "R2") (pin "1") (pinfunction "1_1") (pintype "passive"))
      (node (ref "U4") (pin "20") (pinfunction "SCL_M_20") (pintype "bidirectional"))
      (node (ref "U4") (pin "24") (pinfunction "SCL_A_24") (pintype "bidirectional"))
    )
    (net (code "59") (name "Net-(Q6-S)") (class "Default")
      (node (ref "Q6") (pin "2") (pinfunction "S_2") (pintype "passive"))
      (node (ref "R19") (pin "1") (pinfunction "1_1") (pintype "passive"))
      (node (ref "U4") (pin "19") (pinfunction "SDA_M_19") (pintype "bidirectional"))
      (node (ref "U4") (pin "25") (pinfunction "SDA_A_25") (pintype "bidirectional"))
    )
    (net (code "60") (name "Net-(R18-Pad2)") (class "Default")
      (node (ref "R18") (pin "2") (pinfunction "2_2") (pintype "passive"))
      (node (ref "RSSI") (pin "A") (pinfunction "A_A") (pintype "passive"))
    )
    (net (code "61") (name "Net-(R23-Pad2)") (class "Default")
      (node (ref "R23") (pin "2") (pinfunction "2_2") (pintype "passive"))
      (node (ref "VBATT") (pin "2") (pinfunction "2_2") (pintype "passive"))
    )
    (net (code "62") (name "Net-(R25-Pad2)") (class "Default")
      (node (ref "R25") (pin "2") (pinfunction "2_2") (pintype "passive"))
      (node (ref "VBATT") (pin "1") (pinfunction "1_1") (pintype "passive"))
    )
    (net (code "63") (name "Net-(U$1-RESET)") (class "Default")
      (node (ref "JP1") (pin "6") (pinfunction "6_6") (pintype "passive"))
      (node (ref "U$1") (pin "5") (pinfunction "RESET_5") (pintype "input"))
    )
    (net (code "64") (name "Net-(U2-1Y)") (class "Default")
      (node (ref "U2") (pin "2") (pinfunction "1Y_2") (pintype "bidirectional"))
      (node (ref "U3") (pin "2") (pinfunction "CS_2") (pintype "bidirectional"))
    )
    (net (code "65") (name "Net-(U2-2Y)") (class "Default")
      (node (ref "U2") (pin "4") (pinfunction "2Y_4") (pintype "bidirectional"))
      (node (ref "U3") (pin "3") (pinfunction "DI_3") (pintype "bidirectional"))
    )
    (net (code "66") (name "Net-(U2-3Y)") (class "Default")
      (node (ref "U2") (pin "6") (pinfunction "3Y_6") (pintype "bidirectional"))
      (node (ref "U3") (pin "5") (pinfunction "SCK_5") (pintype "bidirectional"))
    )
    (net (code "67") (name "Net-(U4-C1)") (class "Default")
      (node (ref "C6") (pin "1") (pinfunction "1_1") (pintype "passive"))
      (node (ref "U4") (pin "15") (pinfunction "C1_15") (pintype "bidirectional"))
    )
    (net (code "68") (name "Net-(U4-SET1)") (class "Default")
      (node (ref "C5") (pin "1") (pinfunction "1_1") (pintype "passive"))
      (node (ref "U4") (pin "16") (pinfunction "SET1_16") (pintype "bidirectional"))
    )
    (net (code "69") (name "Net-(U4-SET2)") (class "Default")
      (node (ref "C5") (pin "2") (pinfunction "2_2") (pintype "passive"))
      (node (ref "U4") (pin "12") (pinfunction "SET2_12") (pintype "bidirectional"))
    )
    (net (code "70") (name "Net-(U5-PLL)") (class "Default")
      (node (ref "C10") (pin "1") (pinfunction "1_1") (pintype "passive"))
      (node (ref "C7") (pin "1") (pinfunction "1_1") (pintype "passive"))
      (node (ref "U5") (pin "14") (pinfunction "PLL_14") (pintype "bidirectional"))
    )
    (net (code "71") (name "unconnected-(BMP085-EOC-Pad2)") (class "Default")
      (node (ref "BMP085") (pin "2") (pinfunction "EOC_2") (pintype "output"))
    )
    (net (code "72") (name "unconnected-(BMP085-NC-Pad5)") (class "Default")
      (node (ref "BMP085") (pin "5") (pinfunction "NC_5") (pintype "bidirectional"))
    )
    (net (code "73") (name "unconnected-(BMP085-XCLR-Pad8)") (class "Default")
      (node (ref "BMP085") (pin "8") (pinfunction "XCLR_8") (pintype "input"))
    )
    (net (code "74") (name "unconnected-(ICSP-Pad3)") (class "Default")
      (node (ref "ICSP") (pin "3") (pinfunction "3_3") (pintype "passive"))
    )
    (net (code "75") (name "unconnected-(U1-(A8)PC0-Pad53)") (class "Default")
      (node (ref "U1") (pin "53") (pinfunction "(A8)PC0_53") (pintype "bidirectional"))
    )
    (net (code "76") (name "unconnected-(U1-(A9)PC1-Pad54)") (class "Default")
      (node (ref "U1") (pin "54") (pinfunction "(A9)PC1_54") (pintype "bidirectional"))
    )
    (net (code "77") (name "unconnected-(U1-(A10)PC2-Pad55)") (class "Default")
      (node (ref "U1") (pin "55") (pinfunction "(A10)PC2_55") (pintype "bidirectional"))
    )
    (net (code "78") (name "unconnected-(U1-(A11)PC3-Pad56)") (class "Default")
      (node (ref "U1") (pin "56") (pinfunction "(A11)PC3_56") (pintype "bidirectional"))
    )
    (net (code "79") (name "unconnected-(U1-(A12)PC4-Pad57)") (class "Default")
      (node (ref "U1") (pin "57") (pinfunction "(A12)PC4_57") (pintype "bidirectional"))
    )
    (net (code "80") (name "unconnected-(U1-(A13)PC5-Pad58)") (class "Default")
      (node (ref "U1") (pin "58") (pinfunction "(A13)PC5_58") (pintype "bidirectional"))
    )
    (net (code "81") (name "unconnected-(U1-(A14)PC6-Pad59)") (class "Default")
      (node (ref "U1") (pin "59") (pinfunction "(A14)PC6_59") (pintype "bidirectional"))
    )
    (net (code "82") (name "unconnected-(U1-(A15)PC7-Pad60)") (class "Default")
      (node (ref "U1") (pin "60") (pinfunction "(A15)PC7_60") (pintype "bidirectional"))
    )
    (net (code "83") (name "unconnected-(U1-(AD0)PA0-Pad78)") (class "Default")
      (node (ref "U1") (pin "78") (pinfunction "(AD0)PA0_78") (pintype "bidirectional"))
    )
    (net (code "84") (name "unconnected-(U1-(AD1)PA1-Pad77)") (class "Default")
      (node (ref "U1") (pin "77") (pinfunction "(AD1)PA1_77") (pintype "bidirectional"))
    )
    (net (code "85") (name "unconnected-(U1-(AD2)PA2-Pad76)") (class "Default")
      (node (ref "U1") (pin "76") (pinfunction "(AD2)PA2_76") (pintype "bidirectional"))
    )
    (net (code "86") (name "unconnected-(U1-(AD3)PA3-Pad75)") (class "Default")
      (node (ref "U1") (pin "75") (pinfunction "(AD3)PA3_75") (pintype "bidirectional"))
    )
    (net (code "87") (name "unconnected-(U1-(AD4)PA4-Pad74)") (class "Default")
      (node (ref "U1") (pin "74") (pinfunction "(AD4)PA4_74") (pintype "bidirectional"))
    )
    (net (code "88") (name "unconnected-(U1-(AD5)PA5-Pad73)") (class "Default")
      (node (ref "U1") (pin "73") (pinfunction "(AD5)PA5_73") (pintype "bidirectional"))
    )
    (net (code "89") (name "unconnected-(U1-(AD6)PA6-Pad72)") (class "Default")
      (node (ref "U1") (pin "72") (pinfunction "(AD6)PA6_72") (pintype "bidirectional"))
    )
    (net (code "90") (name "unconnected-(U1-(AD7)PA7-Pad71)") (class "Default")
      (node (ref "U1") (pin "71") (pinfunction "(AD7)PA7_71") (pintype "bidirectional"))
    )
    (net (code "91") (name "unconnected-(U1-(ADC4{slash}TCK)PF4-Pad93)") (class "Default")
      (node (ref "U1") (pin "93") (pinfunction "(ADC4/TCK)PF4_93") (pintype "bidirectional"))
    )
    (net (code "92") (name "unconnected-(U1-(ADC5{slash}TMS)PF5-Pad92)") (class "Default")
      (node (ref "U1") (pin "92") (pinfunction "(ADC5/TMS)PF5_92") (pintype "bidirectional"))
    )
    (net (code "93") (name "unconnected-(U1-(ADC6{slash}TDO)PF6-Pad91)") (class "Default")
      (node (ref "U1") (pin "91") (pinfunction "(ADC6/TDO)PF6_91") (pintype "bidirectional"))
    )
    (net (code "94") (name "unconnected-(U1-(ADC7{slash}TDI)PF7-Pad90)") (class "Default")
      (node (ref "U1") (pin "90") (pinfunction "(ADC7/TDI)PF7_90") (pintype "bidirectional"))
    )
    (net (code "95") (name "unconnected-(U1-(ALE)PG2-Pad70)") (class "Default")
      (node (ref "U1") (pin "70") (pinfunction "(ALE)PG2_70") (pintype "bidirectional"))
    )
    (net (code "96") (name "unconnected-(U1-(CLKO{slash}ICP3{slash}INT7)PE7-Pad9)") (class "Default")
      (node (ref "U1") (pin "9") (pinfunction "(CLKO/ICP3/INT7)PE7_9") (pintype "bidirectional"))
    )
    (net (code "97") (name "unconnected-(U1-(ICP1)PD4-Pad47)") (class "Default")
      (node (ref "U1") (pin "47") (pinfunction "(ICP1)PD4_47") (pintype "bidirectional"))
    )
    (net (code "98") (name "unconnected-(U1-(OC0A{slash}OC1C{slash}PCINT7)PB7-Pad26)") (class "Default")
      (node (ref "U1") (pin "26") (pinfunction "(OC0A/OC1C/PCINT7)PB7_26") (pintype "bidirectional"))
    )
    (net (code "99") (name "unconnected-(U1-(OC0B)PG5-Pad1)") (class "Default")
      (node (ref "U1") (pin "1") (pinfunction "(OC0B)PG5_1") (pintype "bidirectional"))
    )
    (net (code "100") (name "unconnected-(U1-(OC1A{slash}PCINT5)PB5-Pad24)") (class "Default")
      (node (ref "U1") (pin "24") (pinfunction "(OC1A/PCINT5)PB5_24") (pintype "bidirectional"))
    )
    (net (code "101") (name "unconnected-(U1-(OC1B{slash}PCINT6)PB6-Pad25)") (class "Default")
      (node (ref "U1") (pin "25") (pinfunction "(OC1B/PCINT6)PB6_25") (pintype "bidirectional"))
    )
    (net (code "102") (name "unconnected-(U1-(OC2A{slash}PCINT4)PB4-Pad23)") (class "Default")
      (node (ref "U1") (pin "23") (pinfunction "(OC2A/PCINT4)PB4_23") (pintype "bidirectional"))
    )
    (net (code "103") (name "unconnected-(U1-(RD)PG1-Pad52)") (class "Default")
      (node (ref "U1") (pin "52") (pinfunction "(RD)PG1_52") (pintype "bidirectional"))
    )
    (net (code "104") (name "unconnected-(U1-(T0)PD7-Pad50)") (class "Default")
      (node (ref "U1") (pin "50") (pinfunction "(T0)PD7_50") (pintype "bidirectional"))
    )
    (net (code "105") (name "unconnected-(U1-(T1)PD6-Pad49)") (class "Default")
      (node (ref "U1") (pin "49") (pinfunction "(T1)PD6_49") (pintype "bidirectional"))
    )
    (net (code "106") (name "unconnected-(U1-(T3{slash}INT6)PE6-Pad8)") (class "Default")
      (node (ref "U1") (pin "8") (pinfunction "(T3/INT6)PE6_8") (pintype "bidirectional"))
    )
    (net (code "107") (name "unconnected-(U1-(TOSC1)PG4-Pad29)") (class "Default")
      (node (ref "U1") (pin "29") (pinfunction "(TOSC1)PG4_29") (pintype "bidirectional"))
    )
    (net (code "108") (name "unconnected-(U1-(TOSC2)PG3-Pad28)") (class "Default")
      (node (ref "U1") (pin "28") (pinfunction "(TOSC2)PG3_28") (pintype "bidirectional"))
    )
    (net (code "109") (name "unconnected-(U1-(WR)PG0-Pad51)") (class "Default")
      (node (ref "U1") (pin "51") (pinfunction "(WR)PG0_51") (pintype "bidirectional"))
    )
    (net (code "110") (name "unconnected-(U1-(XCK0{slash}AIN0)PE2-Pad4)") (class "Default")
      (node (ref "U1") (pin "4") (pinfunction "(XCK0/AIN0)PE2_4") (pintype "bidirectional"))
    )
    (net (code "111") (name "unconnected-(U1-(XCK1)PD5-Pad48)") (class "Default")
      (node (ref "U1") (pin "48") (pinfunction "(XCK1)PD5_48") (pintype "bidirectional"))
    )
    (net (code "112") (name "unconnected-(U1-PH0(RXD2)-Pad12)") (class "Default")
      (node (ref "U1") (pin "12") (pinfunction "PH0(RXD2)_12") (pintype "bidirectional"))
    )
    (net (code "113") (name "unconnected-(U1-PH1(TXD2)-Pad13)") (class "Default")
      (node (ref "U1") (pin "13") (pinfunction "PH1(TXD2)_13") (pintype "bidirectional"))
    )
    (net (code "114") (name "unconnected-(U1-PH2(XCK2)-Pad14)") (class "Default")
      (node (ref "U1") (pin "14") (pinfunction "PH2(XCK2)_14") (pintype "bidirectional"))
    )
    (net (code "115") (name "unconnected-(U1-PH6(OC2B)-Pad18)") (class "Default")
      (node (ref "U1") (pin "18") (pinfunction "PH6(OC2B)_18") (pintype "bidirectional"))
    )
    (net (code "116") (name "unconnected-(U1-PH7(T4)-Pad27)") (class "Default")
      (node (ref "U1") (pin "27") (pinfunction "PH7(T4)_27") (pintype "bidirectional"))
    )
    (net (code "117") (name "unconnected-(U1-PJ0(RXD3{slash}PCINT9)-Pad63)") (class "Default")
      (node (ref "U1") (pin "63") (pinfunction "PJ0(RXD3/PCINT9)_63") (pintype "bidirectional"))
    )
    (net (code "118") (name "unconnected-(U1-PJ1(TXD3{slash}PCINT10)-Pad64)") (class "Default")
      (node (ref "U1") (pin "64") (pinfunction "PJ1(TXD3/PCINT10)_64") (pintype "bidirectional"))
    )
    (net (code "119") (name "unconnected-(U1-PJ2(XCK3{slash}PCINT11)-Pad65)") (class "Default")
      (node (ref "U1") (pin "65") (pinfunction "PJ2(XCK3/PCINT11)_65") (pintype "bidirectional"))
    )
    (net (code "120") (name "unconnected-(U1-PJ3(PCINT12)-Pad66)") (class "Default")
      (node (ref "U1") (pin "66") (pinfunction "PJ3(PCINT12)_66") (pintype "bidirectional"))
    )
    (net (code "121") (name "unconnected-(U1-PJ4(PCINT13)-Pad67)") (class "Default")
      (node (ref "U1") (pin "67") (pinfunction "PJ4(PCINT13)_67") (pintype "bidirectional"))
    )
    (net (code "122") (name "unconnected-(U1-PJ5(PCINT14)-Pad68)") (class "Default")
      (node (ref "U1") (pin "68") (pinfunction "PJ5(PCINT14)_68") (pintype "bidirectional"))
    )
    (net (code "123") (name "unconnected-(U1-PJ6(PCINT15)-Pad69)") (class "Default")
      (node (ref "U1") (pin "69") (pinfunction "PJ6(PCINT15)_69") (pintype "bidirectional"))
    )
    (net (code "124") (name "unconnected-(U1-PJ7-Pad79)") (class "Default")
      (node (ref "U1") (pin "79") (pinfunction "PJ7_79") (pintype "bidirectional"))
    )
    (net (code "125") (name "unconnected-(U1-PK0(ADC8{slash}PCINT16)-Pad89)") (class "Default")
      (node (ref "U1") (pin "89") (pinfunction "PK0(ADC8/PCINT16)_89") (pintype "bidirectional"))
    )
    (net (code "126") (name "unconnected-(U1-PK1(ADC9{slash}PCINT17)-Pad88)") (class "Default")
      (node (ref "U1") (pin "88") (pinfunction "PK1(ADC9/PCINT17)_88") (pintype "bidirectional"))
    )
    (net (code "127") (name "unconnected-(U1-PK2(ADC10{slash}PCINT18)-Pad87)") (class "Default")
      (node (ref "U1") (pin "87") (pinfunction "PK2(ADC10/PCINT18)_87") (pintype "bidirectional"))
    )
    (net (code "128") (name "unconnected-(U1-PK3(ADC11{slash}PCINT19)-Pad86)") (class "Default")
      (node (ref "U1") (pin "86") (pinfunction "PK3(ADC11/PCINT19)_86") (pintype "bidirectional"))
    )
    (net (code "129") (name "unconnected-(U1-PK4(ADC12{slash}PCINT20)-Pad85)") (class "Default")
      (node (ref "U1") (pin "85") (pinfunction "PK4(ADC12/PCINT20)_85") (pintype "bidirectional"))
    )
    (net (code "130") (name "unconnected-(U1-PK5(ADC13{slash}PCINT21)-Pad84)") (class "Default")
      (node (ref "U1") (pin "84") (pinfunction "PK5(ADC13/PCINT21)_84") (pintype "bidirectional"))
    )
    (net (code "131") (name "unconnected-(U1-PK6(ADC14{slash}PCINT22)-Pad83)") (class "Default")
      (node (ref "U1") (pin "83") (pinfunction "PK6(ADC14/PCINT22)_83") (pintype "bidirectional"))
    )
    (net (code "132") (name "unconnected-(U1-PK7(ADC15{slash}PCINT23)-Pad82)") (class "Default")
      (node (ref "U1") (pin "82") (pinfunction "PK7(ADC15/PCINT23)_82") (pintype "bidirectional"))
    )
    (net (code "133") (name "unconnected-(U1-PL0(ICP4)-Pad35)") (class "Default")
      (node (ref "U1") (pin "35") (pinfunction "PL0(ICP4)_35") (pintype "bidirectional"))
    )
    (net (code "134") (name "unconnected-(U1-PL1(ICP5)-Pad36)") (class "Default")
      (node (ref "U1") (pin "36") (pinfunction "PL1(ICP5)_36") (pintype "bidirectional"))
    )
    (net (code "135") (name "unconnected-(U1-PL2(T5)-Pad37)") (class "Default")
      (node (ref "U1") (pin "37") (pinfunction "PL2(T5)_37") (pintype "bidirectional"))
    )
    (net (code "136") (name "unconnected-(U1-PL5(OC5C)-Pad40)") (class "Default")
      (node (ref "U1") (pin "40") (pinfunction "PL5(OC5C)_40") (pintype "bidirectional"))
    )
    (net (code "137") (name "unconnected-(U1-PL6-Pad41)") (class "Default")
      (node (ref "U1") (pin "41") (pinfunction "PL6_41") (pintype "bidirectional"))
    )
    (net (code "138") (name "unconnected-(U1-PL7-Pad42)") (class "Default")
      (node (ref "U1") (pin "42") (pinfunction "PL7_42") (pintype "bidirectional"))
    )
    (net (code "139") (name "unconnected-(U2-4A-Pad9)") (class "Default")
      (node (ref "U2") (pin "9") (pinfunction "4A_9") (pintype "bidirectional"))
    )
    (net (code "140") (name "unconnected-(U2-4Y-Pad10)") (class "Default")
      (node (ref "U2") (pin "10") (pinfunction "4Y_10") (pintype "bidirectional"))
    )
    (net (code "141") (name "unconnected-(U2-5A-Pad11)") (class "Default")
      (node (ref "U2") (pin "11") (pinfunction "5A_11") (pintype "bidirectional"))
    )
    (net (code "142") (name "unconnected-(U2-5Y-Pad12)") (class "Default")
      (node (ref "U2") (pin "12") (pinfunction "5Y_12") (pintype "bidirectional"))
    )
    (net (code "143") (name "unconnected-(U2-6A-Pad14)") (class "Default")
      (node (ref "U2") (pin "14") (pinfunction "6A_14") (pintype "bidirectional"))
    )
    (net (code "144") (name "unconnected-(U2-6Y-Pad15)") (class "Default")
      (node (ref "U2") (pin "15") (pinfunction "6Y_15") (pintype "bidirectional"))
    )
    (net (code "145") (name "unconnected-(U3-NC-Pad1)") (class "Default")
      (node (ref "U3") (pin "1") (pinfunction "NC_1") (pintype "bidirectional"))
    )
    (net (code "146") (name "unconnected-(U3-RSV-Pad8)") (class "Default")
      (node (ref "U3") (pin "8") (pinfunction "RSV_8") (pintype "bidirectional"))
    )
    (net (code "147") (name "unconnected-(U4-DRDY_M-Pad18)") (class "Default")
      (node (ref "U4") (pin "18") (pinfunction "DRDY_M_18") (pintype "bidirectional"))
    )
    (net (code "148") (name "unconnected-(U4-INT1-Pad26)") (class "Default")
      (node (ref "U4") (pin "26") (pinfunction "INT1_26") (pintype "bidirectional"))
    )
    (net (code "149") (name "unconnected-(U4-INT2-Pad27)") (class "Default")
      (node (ref "U4") (pin "27") (pinfunction "INT2_27") (pintype "bidirectional"))
    )
    (net (code "150") (name "unconnected-(U5-INT1-Pad7)") (class "Default")
      (node (ref "U5") (pin "7") (pinfunction "INT1_7") (pintype "bidirectional"))
    )
    (net (code "151") (name "unconnected-(U5-INT2-Pad6)") (class "Default")
      (node (ref "U5") (pin "6") (pinfunction "INT2_6") (pintype "bidirectional"))
    )
  )
)
